# my.net
KiCad netlist of a schematic drawn in EAGLE
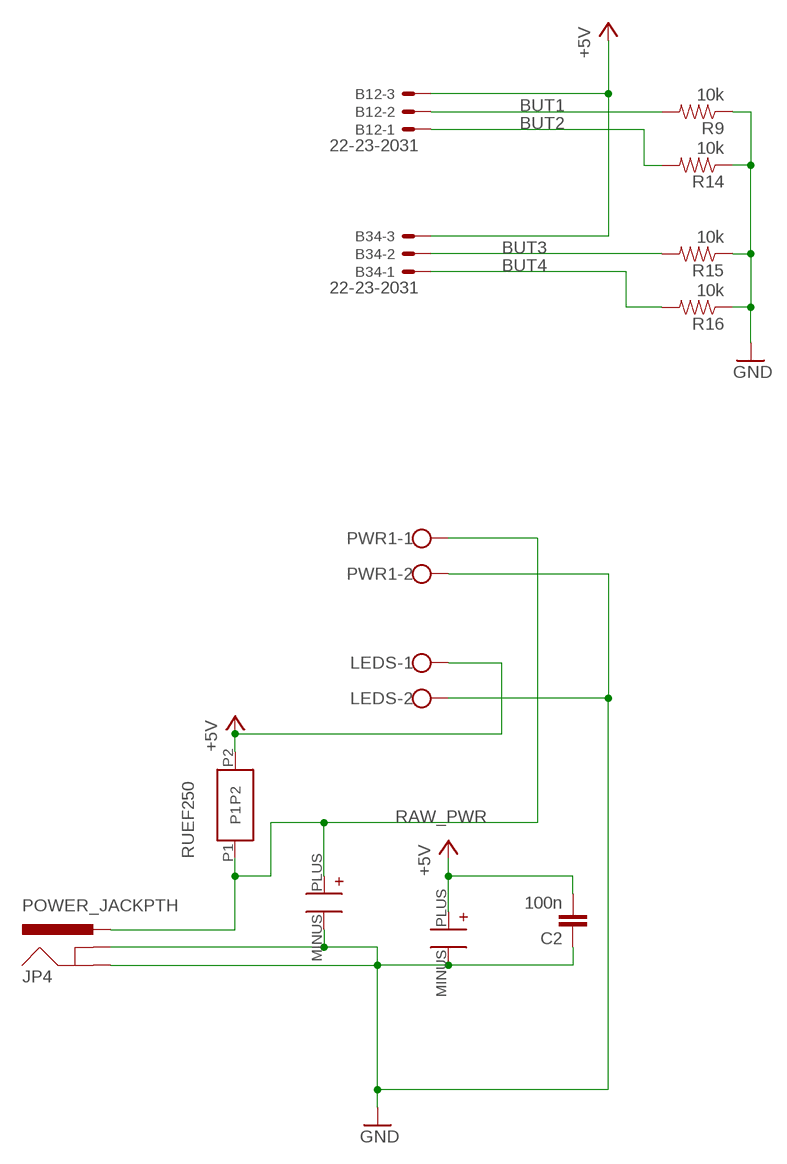
[diagram p0: schematic, sheet 1, part 1 of 2]
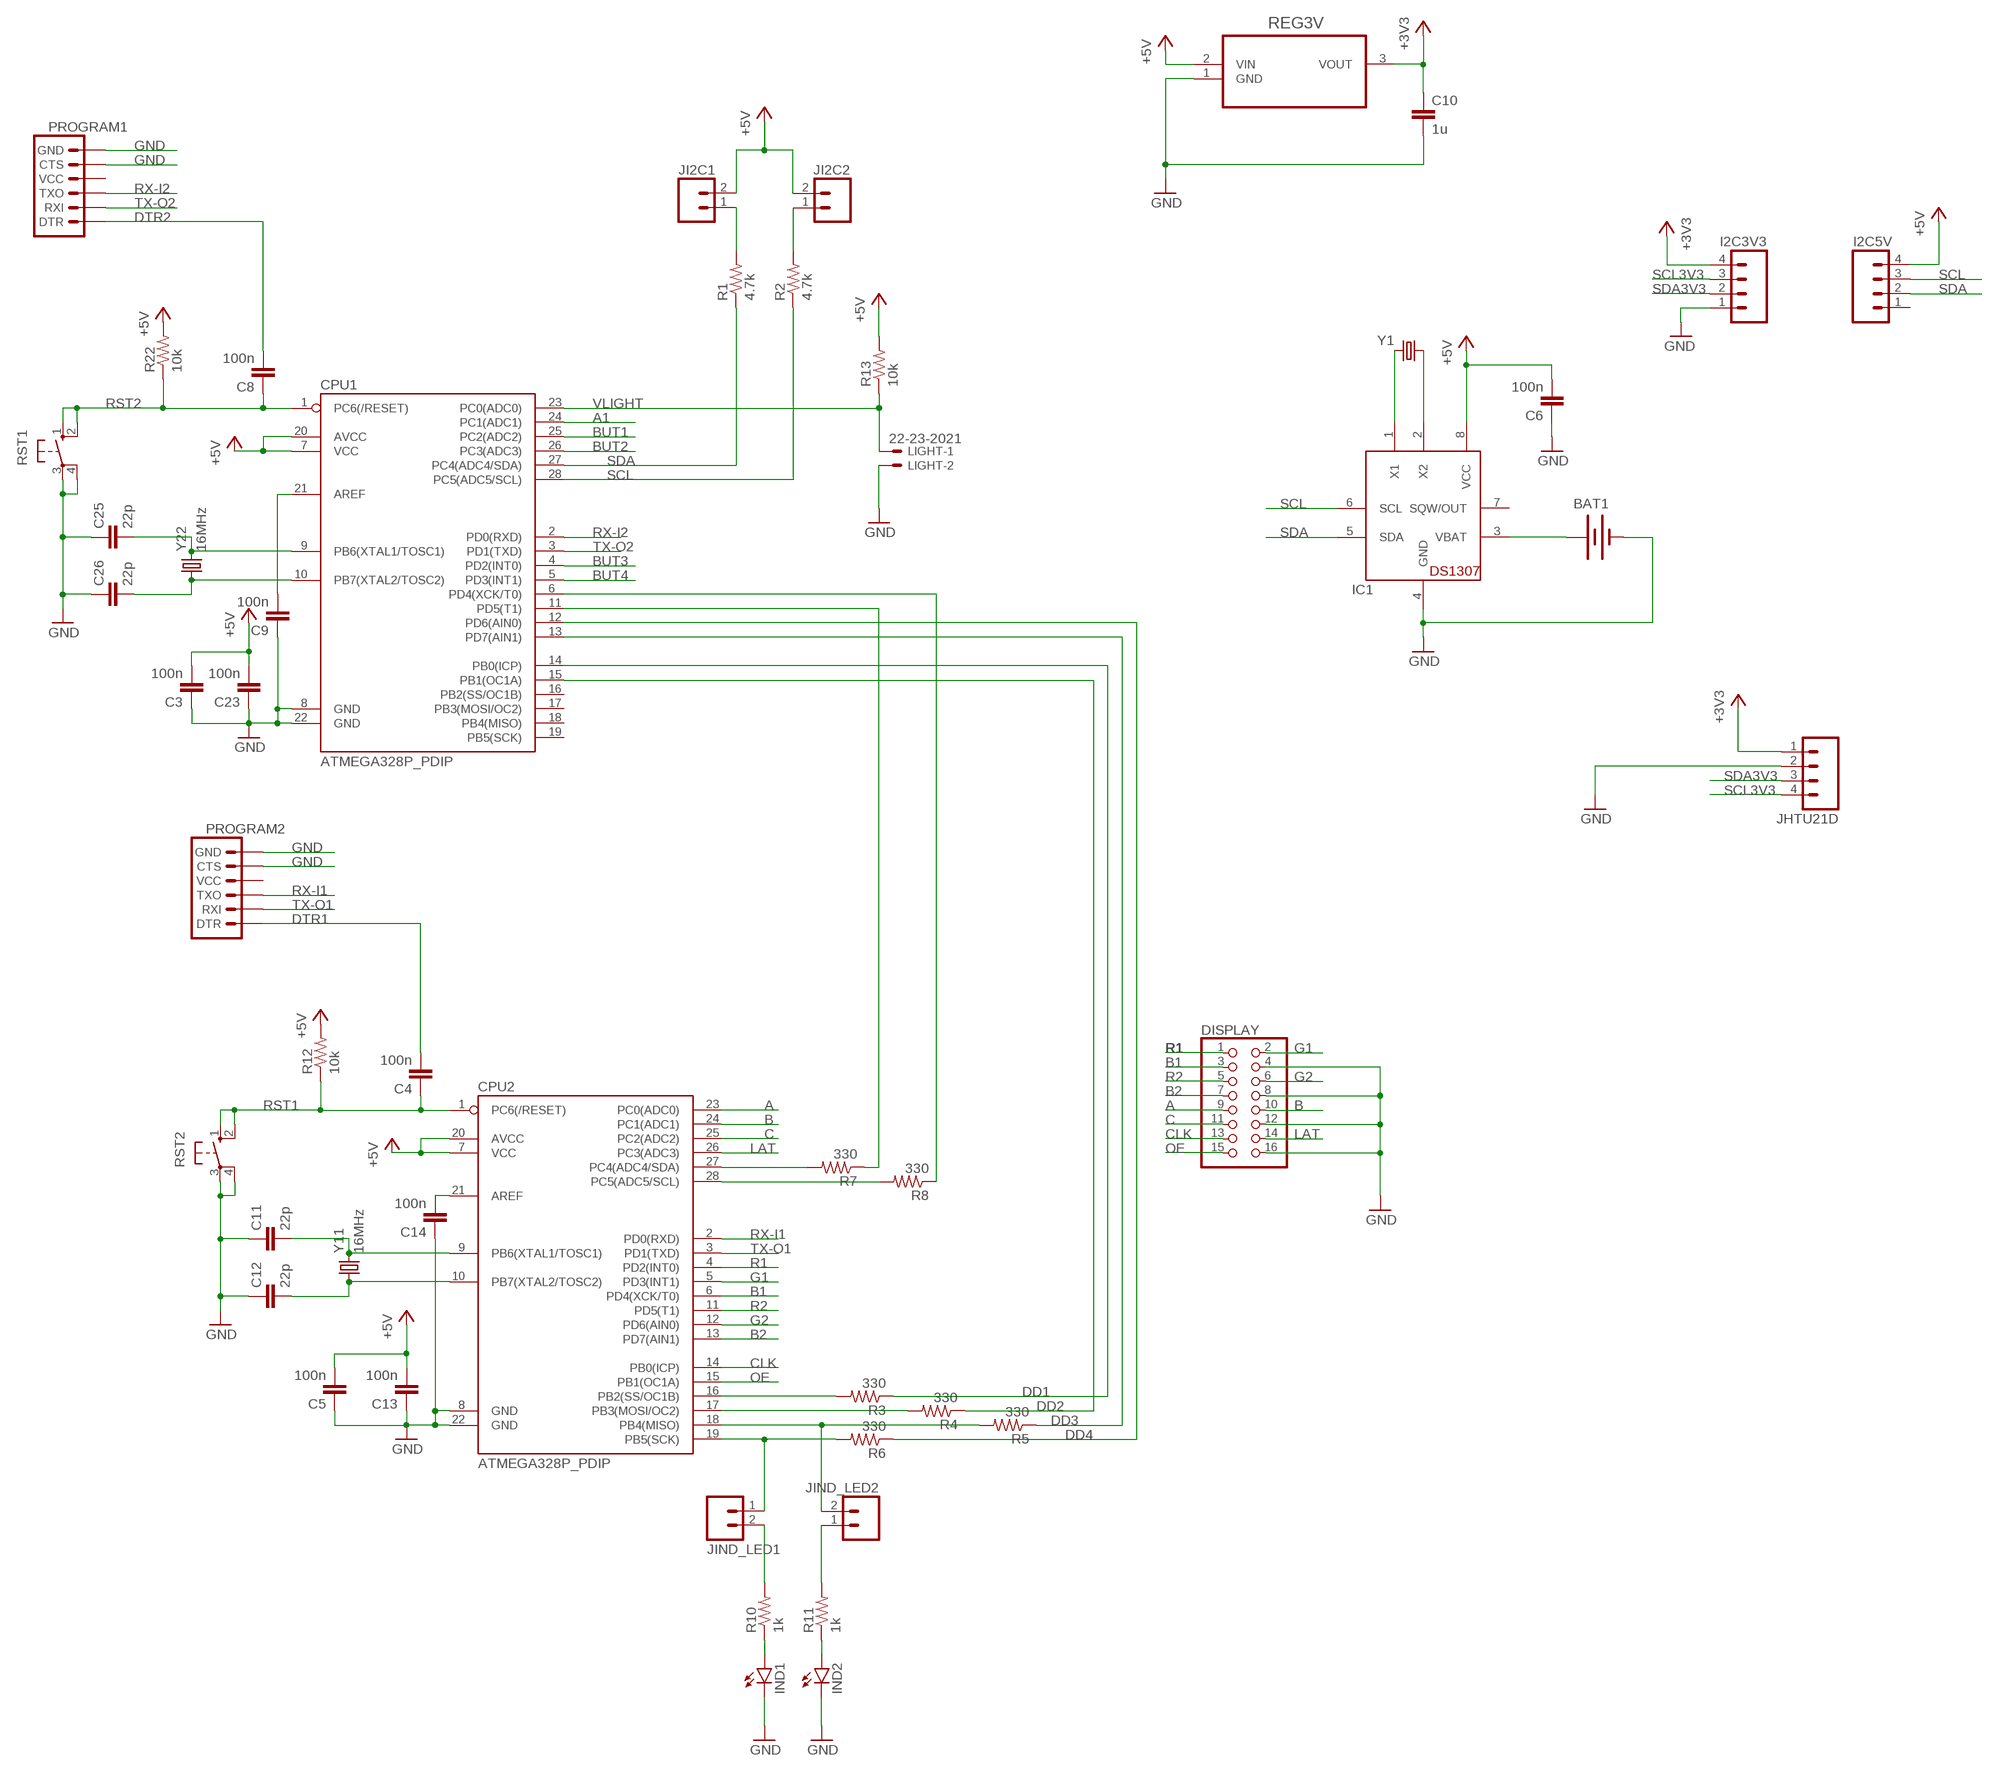
[diagram p1: schematic, sheet 1, part 2 of 2]

(export (version "E")
  (design (tool "Eeschema 10.0.6"))
  (components
    (comp (ref "B12")
      (value "22-23-2031")
      (footprint "eagle-import:22-23-2031")
      (fields (field (name "MF") "MOLEX"))
      (libsource (lib "eagle-import") (part "22-23-2031"))
    )
    (comp (ref "B34")
      (value "22-23-2031")
      (footprint "eagle-import:22-23-2031")
      (fields (field (name "MF") "MOLEX"))
      (libsource (lib "eagle-import") (part "22-23-2031"))
    )
    (comp (ref "BAT1")
      (value "BATTERY12MM")
      (footprint "eagle-import:BATTCON_12MM")
      (libsource (lib "eagle-import") (part "BATTERY12MM"))
    )
    (comp (ref "C1")
      (value "EEU-FR1C471B")
      (footprint "eagle-import:EEU-FR1C471B")
      (libsource (lib "eagle-import") (part "EEU-FR1C471B"))
    )
    (comp (ref "C2")
      (value "100n")
      (footprint "eagle-import:C025-024X044")
      (libsource (lib "eagle-import") (part "C-EU025-024X044"))
    )
    (comp (ref "C3")
      (value "100n")
      (footprint "eagle-import:C025-024X044")
      (libsource (lib "eagle-import") (part "C-EU025-024X044"))
    )
    (comp (ref "C4")
      (value "100n")
      (footprint "eagle-import:C025-024X044")
      (libsource (lib "eagle-import") (part "C-EU025-024X044"))
    )
    (comp (ref "C5")
      (value "100n")
      (footprint "eagle-import:C025-024X044")
      (libsource (lib "eagle-import") (part "C-EU025-024X044"))
    )
    (comp (ref "C6")
      (value "100n")
      (footprint "eagle-import:C025-024X044")
      (libsource (lib "eagle-import") (part "C-EU025-024X044"))
    )
    (comp (ref "C7")
      (value "EEU-FR1C471B")
      (footprint "eagle-import:EEU-FR1C471B")
      (libsource (lib "eagle-import") (part "EEU-FR1C471B"))
    )
    (comp (ref "C8")
      (value "100n")
      (footprint "eagle-import:C025-024X044")
      (libsource (lib "eagle-import") (part "C-EU025-024X044"))
    )
    (comp (ref "C9")
      (value "100n")
      (footprint "eagle-import:C025-024X044")
      (libsource (lib "eagle-import") (part "C-EU025-024X044"))
    )
    (comp (ref "C10")
      (value "1u")
      (footprint "eagle-import:AXIAL-5MM")
      (libsource (lib "eagle-import") (part "CAP_"))
    )
    (comp (ref "C11")
      (value "22p")
      (footprint "eagle-import:C025-024X044")
      (libsource (lib "eagle-import") (part "C-EU025-024X044"))
    )
    (comp (ref "C12")
      (value "22p")
      (footprint "eagle-import:C025-024X044")
      (libsource (lib "eagle-import") (part "C-EU025-024X044"))
    )
    (comp (ref "C13")
      (value "100n")
      (footprint "eagle-import:C025-024X044")
      (libsource (lib "eagle-import") (part "C-EU025-024X044"))
    )
    (comp (ref "C14")
      (value "100n")
      (footprint "eagle-import:C025-024X044")
      (libsource (lib "eagle-import") (part "C-EU025-024X044"))
    )
    (comp (ref "C23")
      (value "100n")
      (footprint "eagle-import:C025-024X044")
      (libsource (lib "eagle-import") (part "C-EU025-024X044"))
    )
    (comp (ref "C25")
      (value "22p")
      (footprint "eagle-import:C025-024X044")
      (libsource (lib "eagle-import") (part "C-EU025-024X044"))
    )
    (comp (ref "C26")
      (value "22p")
      (footprint "eagle-import:C025-024X044")
      (libsource (lib "eagle-import") (part "C-EU025-024X044"))
    )
    (comp (ref "CPU1")
      (value "ATMEGA328P_PDIP")
      (footprint "eagle-import:DIL28-3")
      (libsource (lib "eagle-import") (part "ATMEGA328P_PDIP"))
    )
    (comp (ref "CPU2")
      (value "ATMEGA328P_PDIP")
      (footprint "eagle-import:DIL28-3")
      (libsource (lib "eagle-import") (part "ATMEGA328P_PDIP"))
    )
    (comp (ref "DISPLAY")
      (value "PINHD-2X8")
      (footprint "eagle-import:2X08")
      (libsource (lib "eagle-import") (part "PINHD-2X8"))
    )
    (comp (ref "I2C3V3")
      (value "M04PTH")
      (footprint "eagle-import:1X04")
      (libsource (lib "eagle-import") (part "M04PTH"))
    )
    (comp (ref "I2C5V")
      (value "M04PTH")
      (footprint "eagle-import:1X04")
      (libsource (lib "eagle-import") (part "M04PTH"))
    )
    (comp (ref "IC1")
      (value "DS1307")
      (footprint "eagle-import:DIL08")
      (libsource (lib "eagle-import") (part "DS1307"))
    )
    (comp (ref "IND1")
      (value "LED5MM")
      (footprint "eagle-import:LED5MM")
      (libsource (lib "eagle-import") (part "LED5MM"))
    )
    (comp (ref "IND2")
      (value "LED5MM")
      (footprint "eagle-import:LED5MM")
      (libsource (lib "eagle-import") (part "LED5MM"))
    )
    (comp (ref "JHTU21D")
      (value "M04PTH")
      (footprint "eagle-import:1X04")
      (libsource (lib "eagle-import") (part "M04PTH"))
    )
    (comp (ref "JI2C1")
      (value "M02PTH")
      (footprint "eagle-import:1X02")
      (libsource (lib "eagle-import") (part "M02PTH"))
    )
    (comp (ref "JI2C2")
      (value "M02PTH")
      (footprint "eagle-import:1X02")
      (libsource (lib "eagle-import") (part "M02PTH"))
    )
    (comp (ref "JIND_LED1")
      (value "M02PTH")
      (footprint "eagle-import:1X02")
      (libsource (lib "eagle-import") (part "M02PTH"))
    )
    (comp (ref "JIND_LED2")
      (value "M02PTH")
      (footprint "eagle-import:1X02")
      (libsource (lib "eagle-import") (part "M02PTH"))
    )
    (comp (ref "JP4")
      (value "POWER_JACKPTH")
      (footprint "eagle-import:POWER_JACK_PTH")
      (libsource (lib "eagle-import") (part "POWER_JACKPTH"))
    )
    (comp (ref "LEDS")
      (value "W237-102")
      (footprint "eagle-import:W237-102")
      (fields (field (name "MPN") "237-102"))
      (libsource (lib "eagle-import") (part "W237-102"))
    )
    (comp (ref "LIGHT")
      (value "22-23-2021")
      (footprint "eagle-import:22-23-2021")
      (fields (field (name "MF") "MOLEX"))
      (libsource (lib "eagle-import") (part "22-23-2021"))
    )
    (comp (ref "PROGRAM1")
      (value "ARDUINO_SERIAL_PROGRAMPTH")
      (footprint "eagle-import:1X06")
      (libsource (lib "eagle-import") (part "ARDUINO_SERIAL_PROGRAMPTH"))
    )
    (comp (ref "PROGRAM2")
      (value "ARDUINO_SERIAL_PROGRAMPTH")
      (footprint "eagle-import:1X06")
      (libsource (lib "eagle-import") (part "ARDUINO_SERIAL_PROGRAMPTH"))
    )
    (comp (ref "PWR1")
      (value "W237-102")
      (footprint "eagle-import:W237-102")
      (fields (field (name "MPN") "237-102"))
      (libsource (lib "eagle-import") (part "W237-102"))
    )
    (comp (ref "R1")
      (value "4.7k")
      (footprint "eagle-import:AXIAL-0.3")
      (libsource (lib "eagle-import") (part "RESISTORAXIAL-0.3"))
    )
    (comp (ref "R2")
      (value "4.7k")
      (footprint "eagle-import:AXIAL-0.3")
      (libsource (lib "eagle-import") (part "RESISTORAXIAL-0.3"))
    )
    (comp (ref "R3")
      (value "330")
      (footprint "eagle-import:AXIAL-0.3")
      (libsource (lib "eagle-import") (part "RESISTORAXIAL-0.3"))
    )
    (comp (ref "R4")
      (value "330")
      (footprint "eagle-import:AXIAL-0.3")
      (libsource (lib "eagle-import") (part "RESISTORAXIAL-0.3"))
    )
    (comp (ref "R5")
      (value "330")
      (footprint "eagle-import:AXIAL-0.3")
      (libsource (lib "eagle-import") (part "RESISTORAXIAL-0.3"))
    )
    (comp (ref "R6")
      (value "330")
      (footprint "eagle-import:AXIAL-0.3")
      (libsource (lib "eagle-import") (part "RESISTORAXIAL-0.3"))
    )
    (comp (ref "R7")
      (value "330")
      (footprint "eagle-import:AXIAL-0.3")
      (libsource (lib "eagle-import") (part "RESISTORAXIAL-0.3"))
    )
    (comp (ref "R8")
      (value "330")
      (footprint "eagle-import:AXIAL-0.3")
      (libsource (lib "eagle-import") (part "RESISTORAXIAL-0.3"))
    )
    (comp (ref "R9")
      (value "10k")
      (footprint "eagle-import:AXIAL-0.3")
      (libsource (lib "eagle-import") (part "RESISTORAXIAL-0.3"))
    )
    (comp (ref "R10")
      (value "1k")
      (footprint "eagle-import:AXIAL-0.3")
      (libsource (lib "eagle-import") (part "RESISTORAXIAL-0.3"))
    )
    (comp (ref "R11")
      (value "1k")
      (footprint "eagle-import:AXIAL-0.3")
      (libsource (lib "eagle-import") (part "RESISTORAXIAL-0.3"))
    )
    (comp (ref "R12")
      (value "10k")
      (footprint "eagle-import:AXIAL-0.3")
      (libsource (lib "eagle-import") (part "RESISTORAXIAL-0.3"))
    )
    (comp (ref "R13")
      (value "10k")
      (footprint "eagle-import:AXIAL-0.3")
      (libsource (lib "eagle-import") (part "RESISTORAXIAL-0.3"))
    )
    (comp (ref "R14")
      (value "10k")
      (footprint "eagle-import:AXIAL-0.3")
      (libsource (lib "eagle-import") (part "RESISTORAXIAL-0.3"))
    )
    (comp (ref "R15")
      (value "10k")
      (footprint "eagle-import:AXIAL-0.3")
      (libsource (lib "eagle-import") (part "RESISTORAXIAL-0.3"))
    )
    (comp (ref "R16")
      (value "10k")
      (footprint "eagle-import:AXIAL-0.3")
      (libsource (lib "eagle-import") (part "RESISTORAXIAL-0.3"))
    )
    (comp (ref "R22")
      (value "10k")
      (footprint "eagle-import:AXIAL-0.3")
      (libsource (lib "eagle-import") (part "RESISTORAXIAL-0.3"))
    )
    (comp (ref "REG3V")
      (value "MCP1700-3002E/TO")
      (footprint "eagle-import:TO127P254X495-3")
      (libsource (lib "eagle-import") (part "MCP1700-3002E/TO"))
    )
    (comp (ref "RST1")
      (value "10-XX")
      (footprint "eagle-import:B3F-10XX")
      (fields (field (name "MPN") "B3F-1000"))
      (libsource (lib "eagle-import") (part "10-XX"))
    )
    (comp (ref "RST2")
      (value "10-XX")
      (footprint "eagle-import:B3F-10XX")
      (fields (field (name "MPN") "B3F-1000"))
      (libsource (lib "eagle-import") (part "10-XX"))
    )
    (comp (ref "RUEF250")
      (value "RUEF250U")
      (footprint "eagle-import:RUEF250U")
      (libsource (lib "eagle-import") (part "RUEF250U"))
    )
    (comp (ref "Y1")
      (value "CRYSTAL32-SMD")
      (footprint "eagle-import:CRYSTAL-32KHZ-SMD")
      (libsource (lib "eagle-import") (part "CRYSTAL32-SMD"))
    )
    (comp (ref "Y11")
      (value "16MHz")
      (footprint "eagle-import:HC49US")
      (libsource (lib "eagle-import") (part "CRYSTALHC49US"))
    )
    (comp (ref "Y22")
      (value "16MHz")
      (footprint "eagle-import:HC49US")
      (libsource (lib "eagle-import") (part "CRYSTALHC49US"))
    )
  )
  (nets
    (net (code "1") (name "+3V3") (class "Default")
      (node (ref "C10") (pin "P$1") (pinfunction "1_P$1") (pintype "passive"))
      (node (ref "I2C3V3") (pin "4") (pinfunction "4_4") (pintype "passive"))
      (node (ref "JHTU21D") (pin "1") (pinfunction "1_1") (pintype "passive"))
      (node (ref "REG3V") (pin "3") (pinfunction "VOUT_3") (pintype "output"))
    )
    (net (code "2") (name "+5V") (class "Default")
      (node (ref "B12") (pin "3") (pinfunction "S_3") (pintype "passive"))
      (node (ref "B34") (pin "3") (pinfunction "S_3") (pintype "passive"))
      (node (ref "C1") (pin "PLUS") (pinfunction "PLUS_PLUS") (pintype "bidirectional"))
      (node (ref "C13") (pin "2") (pinfunction "2_2") (pintype "passive"))
      (node (ref "C2") (pin "2") (pinfunction "2_2") (pintype "passive"))
      (node (ref "C23") (pin "2") (pinfunction "2_2") (pintype "passive"))
      (node (ref "C3") (pin "2") (pinfunction "2_2") (pintype "passive"))
      (node (ref "C5") (pin "2") (pinfunction "2_2") (pintype "passive"))
      (node (ref "C6") (pin "2") (pinfunction "2_2") (pintype "passive"))
      (node (ref "CPU1") (pin "20") (pinfunction "AVCC_20") (pintype "bidirectional"))
      (node (ref "CPU1") (pin "7") (pinfunction "VCC_7") (pintype "bidirectional"))
      (node (ref "CPU2") (pin "20") (pinfunction "AVCC_20") (pintype "bidirectional"))
      (node (ref "CPU2") (pin "7") (pinfunction "VCC_7") (pintype "bidirectional"))
      (node (ref "I2C5V") (pin "4") (pinfunction "4_4") (pintype "passive"))
      (node (ref "IC1") (pin "8") (pinfunction "VCC_8") (pintype "power_in"))
      (node (ref "JI2C1") (pin "2") (pinfunction "2_2") (pintype "passive"))
      (node (ref "JI2C2") (pin "2") (pinfunction "2_2") (pintype "passive"))
      (node (ref "LEDS") (pin "1") (pinfunction "KL_1") (pintype "passive"))
      (node (ref "R12") (pin "P$2") (pinfunction "2_P$2") (pintype "passive"))
      (node (ref "R13") (pin "P$2") (pinfunction "2_P$2") (pintype "passive"))
      (node (ref "R22") (pin "P$2") (pinfunction "2_P$2") (pintype "passive"))
      (node (ref "REG3V") (pin "2") (pinfunction "VIN_2") (pintype "input"))
      (node (ref "RUEF250") (pin "P2") (pinfunction "P2_P2") (pintype "bidirectional"))
    )
    (net (code "3") (name "/A") (class "Default")
      (node (ref "CPU2") (pin "23") (pinfunction "PC0(ADC0)_23") (pintype "bidirectional"))
      (node (ref "DISPLAY") (pin "9") (pinfunction "9_9") (pintype "passive"))
    )
    (net (code "4") (name "/A1") (class "Default")
      (node (ref "CPU1") (pin "24") (pinfunction "PC1(ADC1)_24") (pintype "bidirectional"))
    )
    (net (code "5") (name "/B") (class "Default")
      (node (ref "CPU2") (pin "24") (pinfunction "PC1(ADC1)_24") (pintype "bidirectional"))
      (node (ref "DISPLAY") (pin "10") (pinfunction "10_10") (pintype "passive"))
    )
    (net (code "6") (name "/B1") (class "Default")
      (node (ref "CPU2") (pin "6") (pinfunction "PD4(XCK/T0)_6") (pintype "bidirectional"))
      (node (ref "DISPLAY") (pin "3") (pinfunction "3_3") (pintype "passive"))
    )
    (net (code "7") (name "/B2") (class "Default")
      (node (ref "CPU2") (pin "13") (pinfunction "PD7(AIN1)_13") (pintype "bidirectional"))
      (node (ref "DISPLAY") (pin "7") (pinfunction "7_7") (pintype "passive"))
    )
    (net (code "8") (name "/BUT1") (class "Default")
      (node (ref "B12") (pin "2") (pinfunction "S_2") (pintype "passive"))
      (node (ref "CPU1") (pin "25") (pinfunction "PC2(ADC2)_25") (pintype "bidirectional"))
      (node (ref "R9") (pin "P$2") (pinfunction "2_P$2") (pintype "passive"))
    )
    (net (code "9") (name "/BUT2") (class "Default")
      (node (ref "B12") (pin "1") (pinfunction "S_1") (pintype "passive"))
      (node (ref "CPU1") (pin "26") (pinfunction "PC3(ADC3)_26") (pintype "bidirectional"))
      (node (ref "R14") (pin "P$2") (pinfunction "2_P$2") (pintype "passive"))
    )
    (net (code "10") (name "/BUT3") (class "Default")
      (node (ref "B34") (pin "2") (pinfunction "S_2") (pintype "passive"))
      (node (ref "CPU1") (pin "4") (pinfunction "PD2(INT0)_4") (pintype "bidirectional"))
      (node (ref "R15") (pin "P$2") (pinfunction "2_P$2") (pintype "passive"))
    )
    (net (code "11") (name "/BUT4") (class "Default")
      (node (ref "B34") (pin "1") (pinfunction "S_1") (pintype "passive"))
      (node (ref "CPU1") (pin "5") (pinfunction "PD3(INT1)_5") (pintype "bidirectional"))
      (node (ref "R16") (pin "P$2") (pinfunction "2_P$2") (pintype "passive"))
    )
    (net (code "12") (name "/C") (class "Default")
      (node (ref "CPU2") (pin "25") (pinfunction "PC2(ADC2)_25") (pintype "bidirectional"))
      (node (ref "DISPLAY") (pin "11") (pinfunction "11_11") (pintype "passive"))
    )
    (net (code "13") (name "/CLK") (class "Default")
      (node (ref "CPU2") (pin "14") (pinfunction "PB0(ICP)_14") (pintype "bidirectional"))
      (node (ref "DISPLAY") (pin "13") (pinfunction "13_13") (pintype "passive"))
    )
    (net (code "14") (name "/DD1") (class "Default")
      (node (ref "CPU1") (pin "14") (pinfunction "PB0(ICP)_14") (pintype "bidirectional"))
      (node (ref "R3") (pin "P$1") (pinfunction "1_P$1") (pintype "passive"))
    )
    (net (code "15") (name "/DD2") (class "Default")
      (node (ref "CPU1") (pin "15") (pinfunction "PB1(OC1A)_15") (pintype "bidirectional"))
      (node (ref "R4") (pin "P$1") (pinfunction "1_P$1") (pintype "passive"))
    )
    (net (code "16") (name "/DD3") (class "Default")
      (node (ref "CPU1") (pin "13") (pinfunction "PD7(AIN1)_13") (pintype "bidirectional"))
      (node (ref "R5") (pin "P$1") (pinfunction "1_P$1") (pintype "passive"))
    )
    (net (code "17") (name "/DD4") (class "Default")
      (node (ref "CPU1") (pin "12") (pinfunction "PD6(AIN0)_12") (pintype "bidirectional"))
      (node (ref "R6") (pin "P$1") (pinfunction "1_P$1") (pintype "passive"))
    )
    (net (code "18") (name "/DTR1") (class "Default")
      (node (ref "C4") (pin "2") (pinfunction "2_2") (pintype "passive"))
      (node (ref "PROGRAM2") (pin "1") (pinfunction "DTR_1") (pintype "passive"))
    )
    (net (code "19") (name "/DTR2") (class "Default")
      (node (ref "C8") (pin "2") (pinfunction "2_2") (pintype "passive"))
      (node (ref "PROGRAM1") (pin "1") (pinfunction "DTR_1") (pintype "passive"))
    )
    (net (code "20") (name "/G1") (class "Default")
      (node (ref "CPU2") (pin "5") (pinfunction "PD3(INT1)_5") (pintype "bidirectional"))
      (node (ref "DISPLAY") (pin "2") (pinfunction "2_2") (pintype "passive"))
    )
    (net (code "21") (name "/G2") (class "Default")
      (node (ref "CPU2") (pin "12") (pinfunction "PD6(AIN0)_12") (pintype "bidirectional"))
      (node (ref "DISPLAY") (pin "6") (pinfunction "6_6") (pintype "passive"))
    )
    (net (code "22") (name "/LAT") (class "Default")
      (node (ref "CPU2") (pin "26") (pinfunction "PC3(ADC3)_26") (pintype "bidirectional"))
      (node (ref "DISPLAY") (pin "14") (pinfunction "14_14") (pintype "passive"))
    )
    (net (code "23") (name "/OE") (class "Default")
      (node (ref "CPU2") (pin "15") (pinfunction "PB1(OC1A)_15") (pintype "bidirectional"))
      (node (ref "DISPLAY") (pin "15") (pinfunction "15_15") (pintype "passive"))
    )
    (net (code "24") (name "/R1") (class "Default")
      (node (ref "CPU2") (pin "4") (pinfunction "PD2(INT0)_4") (pintype "bidirectional"))
      (node (ref "DISPLAY") (pin "1") (pinfunction "1_1") (pintype "passive"))
    )
    (net (code "25") (name "/R2") (class "Default")
      (node (ref "CPU2") (pin "11") (pinfunction "PD5(T1)_11") (pintype "bidirectional"))
      (node (ref "DISPLAY") (pin "5") (pinfunction "5_5") (pintype "passive"))
    )
    (net (code "26") (name "/RAW_PWR") (class "Default")
      (node (ref "C7") (pin "PLUS") (pinfunction "PLUS_PLUS") (pintype "bidirectional"))
      (node (ref "JP4") (pin "PWR") (pinfunction "PWR_PWR") (pintype "bidirectional"))
      (node (ref "PWR1") (pin "1") (pinfunction "KL_1") (pintype "passive"))
      (node (ref "RUEF250") (pin "P1") (pinfunction "P1_P1") (pintype "bidirectional"))
    )
    (net (code "27") (name "/RST1") (class "Default")
      (node (ref "C4") (pin "1") (pinfunction "1_1") (pintype "passive"))
      (node (ref "CPU2") (pin "1") (pinfunction "PC6(/RESET)_1") (pintype "bidirectional"))
      (node (ref "R12") (pin "P$1") (pinfunction "1_P$1") (pintype "passive"))
      (node (ref "RST2") (pin "1") (pinfunction "S_1") (pintype "passive"))
      (node (ref "RST2") (pin "2") (pinfunction "S1_2") (pintype "passive"))
    )
    (net (code "28") (name "/RST2") (class "Default")
      (node (ref "C8") (pin "1") (pinfunction "1_1") (pintype "passive"))
      (node (ref "CPU1") (pin "1") (pinfunction "PC6(/RESET)_1") (pintype "bidirectional"))
      (node (ref "R22") (pin "P$1") (pinfunction "1_P$1") (pintype "passive"))
      (node (ref "RST1") (pin "1") (pinfunction "S_1") (pintype "passive"))
      (node (ref "RST1") (pin "2") (pinfunction "S1_2") (pintype "passive"))
    )
    (net (code "29") (name "/RX-I1") (class "Default")
      (node (ref "CPU2") (pin "2") (pinfunction "PD0(RXD)_2") (pintype "bidirectional"))
      (node (ref "PROGRAM2") (pin "3") (pinfunction "TXO_3") (pintype "passive"))
    )
    (net (code "30") (name "/RX-I2") (class "Default")
      (node (ref "CPU1") (pin "2") (pinfunction "PD0(RXD)_2") (pintype "bidirectional"))
      (node (ref "PROGRAM1") (pin "3") (pinfunction "TXO_3") (pintype "passive"))
    )
    (net (code "31") (name "/SCL") (class "Default")
      (node (ref "CPU1") (pin "28") (pinfunction "PC5(ADC5/SCL)_28") (pintype "bidirectional"))
      (node (ref "I2C5V") (pin "3") (pinfunction "3_3") (pintype "passive"))
      (node (ref "IC1") (pin "6") (pinfunction "SCL_6") (pintype "bidirectional"))
      (node (ref "R2") (pin "P$1") (pinfunction "1_P$1") (pintype "passive"))
    )
    (net (code "32") (name "/SCL3V3") (class "Default")
      (node (ref "I2C3V3") (pin "3") (pinfunction "3_3") (pintype "passive"))
      (node (ref "JHTU21D") (pin "4") (pinfunction "4_4") (pintype "passive"))
    )
    (net (code "33") (name "/SDA") (class "Default")
      (node (ref "CPU1") (pin "27") (pinfunction "PC4(ADC4/SDA)_27") (pintype "bidirectional"))
      (node (ref "I2C5V") (pin "2") (pinfunction "2_2") (pintype "passive"))
      (node (ref "IC1") (pin "5") (pinfunction "SDA_5") (pintype "bidirectional"))
      (node (ref "R1") (pin "P$1") (pinfunction "1_P$1") (pintype "passive"))
    )
    (net (code "34") (name "/SDA3V3") (class "Default")
      (node (ref "I2C3V3") (pin "2") (pinfunction "2_2") (pintype "passive"))
      (node (ref "JHTU21D") (pin "3") (pinfunction "3_3") (pintype "passive"))
    )
    (net (code "35") (name "/TX-O1") (class "Default")
      (node (ref "CPU2") (pin "3") (pinfunction "PD1(TXD)_3") (pintype "bidirectional"))
      (node (ref "PROGRAM2") (pin "2") (pinfunction "RXI_2") (pintype "passive"))
    )
    (net (code "36") (name "/TX-O2") (class "Default")
      (node (ref "CPU1") (pin "3") (pinfunction "PD1(TXD)_3") (pintype "bidirectional"))
      (node (ref "PROGRAM1") (pin "2") (pinfunction "RXI_2") (pintype "passive"))
    )
    (net (code "37") (name "/VLIGHT") (class "Default")
      (node (ref "CPU1") (pin "23") (pinfunction "PC0(ADC0)_23") (pintype "bidirectional"))
      (node (ref "LIGHT") (pin "1") (pinfunction "S_1") (pintype "passive"))
      (node (ref "R13") (pin "P$1") (pinfunction "1_P$1") (pintype "passive"))
    )
    (net (code "38") (name "GND") (class "Default")
      (node (ref "BAT1") (pin "GND") (pinfunction "-_GND") (pintype "power_in"))
      (node (ref "C1") (pin "MINUS") (pinfunction "MINUS_MINUS") (pintype "bidirectional"))
      (node (ref "C10") (pin "P$2") (pinfunction "2_P$2") (pintype "passive"))
      (node (ref "C11") (pin "1") (pinfunction "1_1") (pintype "passive"))
      (node (ref "C12") (pin "1") (pinfunction "1_1") (pintype "passive"))
      (node (ref "C13") (pin "1") (pinfunction "1_1") (pintype "passive"))
      (node (ref "C14") (pin "1") (pinfunction "1_1") (pintype "passive"))
      (node (ref "C2") (pin "1") (pinfunction "1_1") (pintype "passive"))
      (node (ref "C23") (pin "1") (pinfunction "1_1") (pintype "passive"))
      (node (ref "C25") (pin "1") (pinfunction "1_1") (pintype "passive"))
      (node (ref "C26") (pin "1") (pinfunction "1_1") (pintype "passive"))
      (node (ref "C3") (pin "1") (pinfunction "1_1") (pintype "passive"))
      (node (ref "C5") (pin "1") (pinfunction "1_1") (pintype "passive"))
      (node (ref "C6") (pin "1") (pinfunction "1_1") (pintype "passive"))
      (node (ref "C7") (pin "MINUS") (pinfunction "MINUS_MINUS") (pintype "bidirectional"))
      (node (ref "C9") (pin "1") (pinfunction "1_1") (pintype "passive"))
      (node (ref "CPU1") (pin "22") (pinfunction "GND_22") (pintype "bidirectional"))
      (node (ref "CPU1") (pin "8") (pinfunction "GND_8") (pintype "bidirectional"))
      (node (ref "CPU2") (pin "22") (pinfunction "GND_22") (pintype "bidirectional"))
      (node (ref "CPU2") (pin "8") (pinfunction "GND_8") (pintype "bidirectional"))
      (node (ref "DISPLAY") (pin "12") (pinfunction "12_12") (pintype "passive"))
      (node (ref "DISPLAY") (pin "16") (pinfunction "16_16") (pintype "passive"))
      (node (ref "DISPLAY") (pin "4") (pinfunction "4_4") (pintype "passive"))
      (node (ref "DISPLAY") (pin "8") (pinfunction "8_8") (pintype "passive"))
      (node (ref "I2C3V3") (pin "1") (pinfunction "1_1") (pintype "passive"))
      (node (ref "IC1") (pin "4") (pinfunction "GND_4") (pintype "power_in"))
      (node (ref "IND1") (pin "K") (pinfunction "C_K") (pintype "passive"))
      (node (ref "IND2") (pin "K") (pinfunction "C_K") (pintype "passive"))
      (node (ref "JHTU21D") (pin "2") (pinfunction "2_2") (pintype "passive"))
      (node (ref "JP4") (pin "GND") (pinfunction "GND_GND") (pintype "bidirectional"))
      (node (ref "JP4") (pin "GNDBREAK") (pinfunction "GNDBREAK_GNDBREAK") (pintype "bidirectional"))
      (node (ref "LEDS") (pin "2") (pinfunction "KL_2") (pintype "passive"))
      (node (ref "LIGHT") (pin "2") (pinfunction "S_2") (pintype "passive"))
      (node (ref "PROGRAM1") (pin "5") (pinfunction "CTS_5") (pintype "passive"))
      (node (ref "PROGRAM1") (pin "6") (pinfunction "GND_6") (pintype "passive"))
      (node (ref "PROGRAM2") (pin "5") (pinfunction "CTS_5") (pintype "passive"))
      (node (ref "PROGRAM2") (pin "6") (pinfunction "GND_6") (pintype "passive"))
      (node (ref "PWR1") (pin "2") (pinfunction "KL_2") (pintype "passive"))
      (node (ref "R14") (pin "P$1") (pinfunction "1_P$1") (pintype "passive"))
      (node (ref "R15") (pin "P$1") (pinfunction "1_P$1") (pintype "passive"))
      (node (ref "R16") (pin "P$1") (pinfunction "1_P$1") (pintype "passive"))
      (node (ref "R9") (pin "P$1") (pinfunction "1_P$1") (pintype "passive"))
      (node (ref "REG3V") (pin "1") (pinfunction "GND_1") (pintype "passive"))
      (node (ref "RST1") (pin "3") (pinfunction "P_3") (pintype "passive"))
      (node (ref "RST1") (pin "4") (pinfunction "P1_4") (pintype "passive"))
      (node (ref "RST2") (pin "3") (pinfunction "P_3") (pintype "passive"))
      (node (ref "RST2") (pin "4") (pinfunction "P1_4") (pintype "passive"))
    )
    (net (code "39") (name "Net-(BAT1-+)") (class "Default")
      (node (ref "BAT1") (pin "PWR@1") (pinfunction "+_PWR@1") (pintype "power_in"))
      (node (ref "IC1") (pin "3") (pinfunction "VBAT_3") (pintype "power_in"))
    )
    (net (code "40") (name "Net-(CPU1-AREF)") (class "Default")
      (node (ref "C9") (pin "2") (pinfunction "2_2") (pintype "passive"))
      (node (ref "CPU1") (pin "21") (pinfunction "AREF_21") (pintype "bidirectional"))
    )
    (net (code "41") (name "Net-(CPU1-PB6(XTAL1{slash}TOSC1))") (class "Default")
      (node (ref "C25") (pin "2") (pinfunction "2_2") (pintype "passive"))
      (node (ref "CPU1") (pin "9") (pinfunction "PB6(XTAL1/TOSC1)_9") (pintype "bidirectional"))
      (node (ref "Y22") (pin "2") (pinfunction "2_2") (pintype "passive"))
    )
    (net (code "42") (name "Net-(CPU1-PB7(XTAL2{slash}TOSC2))") (class "Default")
      (node (ref "C26") (pin "2") (pinfunction "2_2") (pintype "passive"))
      (node (ref "CPU1") (pin "10") (pinfunction "PB7(XTAL2/TOSC2)_10") (pintype "bidirectional"))
      (node (ref "Y22") (pin "1") (pinfunction "1_1") (pintype "passive"))
    )
    (net (code "43") (name "Net-(CPU1-PD4(XCK{slash}T0))") (class "Default")
      (node (ref "CPU1") (pin "6") (pinfunction "PD4(XCK/T0)_6") (pintype "bidirectional"))
      (node (ref "R8") (pin "P$1") (pinfunction "1_P$1") (pintype "passive"))
    )
    (net (code "44") (name "Net-(CPU1-PD5(T1))") (class "Default")
      (node (ref "CPU1") (pin "11") (pinfunction "PD5(T1)_11") (pintype "bidirectional"))
      (node (ref "R7") (pin "P$1") (pinfunction "1_P$1") (pintype "passive"))
    )
    (net (code "45") (name "Net-(CPU2-AREF)") (class "Default")
      (node (ref "C14") (pin "2") (pinfunction "2_2") (pintype "passive"))
      (node (ref "CPU2") (pin "21") (pinfunction "AREF_21") (pintype "bidirectional"))
    )
    (net (code "46") (name "Net-(CPU2-PB2(SS{slash}OC1B))") (class "Default")
      (node (ref "CPU2") (pin "16") (pinfunction "PB2(SS/OC1B)_16") (pintype "bidirectional"))
      (node (ref "R3") (pin "P$2") (pinfunction "2_P$2") (pintype "passive"))
    )
    (net (code "47") (name "Net-(CPU2-PB3(MOSI{slash}OC2))") (class "Default")
      (node (ref "CPU2") (pin "17") (pinfunction "PB3(MOSI/OC2)_17") (pintype "bidirectional"))
      (node (ref "R4") (pin "P$2") (pinfunction "2_P$2") (pintype "passive"))
    )
    (net (code "48") (name "Net-(CPU2-PB4(MISO))") (class "Default")
      (node (ref "CPU2") (pin "18") (pinfunction "PB4(MISO)_18") (pintype "bidirectional"))
      (node (ref "JIND_LED2") (pin "2") (pinfunction "2_2") (pintype "passive"))
      (node (ref "R5") (pin "P$2") (pinfunction "2_P$2") (pintype "passive"))
    )
    (net (code "49") (name "Net-(CPU2-PB5(SCK))") (class "Default")
      (node (ref "CPU2") (pin "19") (pinfunction "PB5(SCK)_19") (pintype "bidirectional"))
      (node (ref "JIND_LED1") (pin "1") (pinfunction "1_1") (pintype "passive"))
      (node (ref "R6") (pin "P$2") (pinfunction "2_P$2") (pintype "passive"))
    )
    (net (code "50") (name "Net-(CPU2-PB6(XTAL1{slash}TOSC1))") (class "Default")
      (node (ref "C11") (pin "2") (pinfunction "2_2") (pintype "passive"))
      (node (ref "CPU2") (pin "9") (pinfunction "PB6(XTAL1/TOSC1)_9") (pintype "bidirectional"))
      (node (ref "Y11") (pin "2") (pinfunction "2_2") (pintype "passive"))
    )
    (net (code "51") (name "Net-(CPU2-PB7(XTAL2{slash}TOSC2))") (class "Default")
      (node (ref "C12") (pin "2") (pinfunction "2_2") (pintype "passive"))
      (node (ref "CPU2") (pin "10") (pinfunction "PB7(XTAL2/TOSC2)_10") (pintype "bidirectional"))
      (node (ref "Y11") (pin "1") (pinfunction "1_1") (pintype "passive"))
    )
    (net (code "52") (name "Net-(CPU2-PC4(ADC4{slash}SDA))") (class "Default")
      (node (ref "CPU2") (pin "27") (pinfunction "PC4(ADC4/SDA)_27") (pintype "bidirectional"))
      (node (ref "R7") (pin "P$2") (pinfunction "2_P$2") (pintype "passive"))
    )
    (net (code "53") (name "Net-(CPU2-PC5(ADC5{slash}SCL))") (class "Default")
      (node (ref "CPU2") (pin "28") (pinfunction "PC5(ADC5/SCL)_28") (pintype "bidirectional"))
      (node (ref "R8") (pin "P$2") (pinfunction "2_P$2") (pintype "passive"))
    )
    (net (code "54") (name "Net-(IC1-X1)") (class "Default")
      (node (ref "IC1") (pin "1") (pinfunction "X1_1") (pintype "passive"))
      (node (ref "Y1") (pin "X2") (pinfunction "2_X2") (pintype "passive"))
    )
    (net (code "55") (name "Net-(IC1-X2)") (class "Default")
      (node (ref "IC1") (pin "2") (pinfunction "X2_2") (pintype "passive"))
      (node (ref "Y1") (pin "X1") (pinfunction "1_X1") (pintype "passive"))
    )
    (net (code "56") (name "Net-(R1-2)") (class "Default")
      (node (ref "JI2C1") (pin "1") (pinfunction "1_1") (pintype "passive"))
      (node (ref "R1") (pin "P$2") (pinfunction "2_P$2") (pintype "passive"))
    )
    (net (code "57") (name "Net-(R2-2)") (class "Default")
      (node (ref "JI2C2") (pin "1") (pinfunction "1_1") (pintype "passive"))
      (node (ref "R2") (pin "P$2") (pinfunction "2_P$2") (pintype "passive"))
    )
    (net (code "58") (name "Net-(R10-1)") (class "Default")
      (node (ref "IND1") (pin "A") (pinfunction "A_A") (pintype "passive"))
      (node (ref "R10") (pin "P$1") (pinfunction "1_P$1") (pintype "passive"))
    )
    (net (code "59") (name "Net-(R10-2)") (class "Default")
      (node (ref "JIND_LED1") (pin "2") (pinfunction "2_2") (pintype "passive"))
      (node (ref "R10") (pin "P$2") (pinfunction "2_P$2") (pintype "passive"))
    )
    (net (code "60") (name "Net-(R11-1)") (class "Default")
      (node (ref "IND2") (pin "A") (pinfunction "A_A") (pintype "passive"))
      (node (ref "R11") (pin "P$1") (pinfunction "1_P$1") (pintype "passive"))
    )
    (net (code "61") (name "Net-(R11-2)") (class "Default")
      (node (ref "JIND_LED2") (pin "1") (pinfunction "1_1") (pintype "passive"))
      (node (ref "R11") (pin "P$2") (pinfunction "2_P$2") (pintype "passive"))
    )
    (net (code "62") (name "unconnected-(CPU1-PB2(SS{slash}OC1B)-Pad16)") (class "Default")
      (node (ref "CPU1") (pin "16") (pinfunction "PB2(SS/OC1B)_16") (pintype "bidirectional"))
    )
    (net (code "63") (name "unconnected-(CPU1-PB3(MOSI{slash}OC2)-Pad17)") (class "Default")
      (node (ref "CPU1") (pin "17") (pinfunction "PB3(MOSI/OC2)_17") (pintype "bidirectional"))
    )
    (net (code "64") (name "unconnected-(CPU1-PB4(MISO)-Pad18)") (class "Default")
      (node (ref "CPU1") (pin "18") (pinfunction "PB4(MISO)_18") (pintype "bidirectional"))
    )
    (net (code "65") (name "unconnected-(CPU1-PB5(SCK)-Pad19)") (class "Default")
      (node (ref "CPU1") (pin "19") (pinfunction "PB5(SCK)_19") (pintype "bidirectional"))
    )
    (net (code "66") (name "unconnected-(I2C5V-Pad1)") (class "Default")
      (node (ref "I2C5V") (pin "1") (pinfunction "1_1") (pintype "passive"))
    )
    (net (code "67") (name "unconnected-(IC1-SQW{slash}OUT-Pad7)") (class "Default")
      (node (ref "IC1") (pin "7") (pinfunction "SQW/OUT_7") (pintype "bidirectional"))
    )
    (net (code "68") (name "unconnected-(PROGRAM1-VCC-Pad4)") (class "Default")
      (node (ref "PROGRAM1") (pin "4") (pinfunction "VCC_4") (pintype "passive"))
    )
    (net (code "69") (name "unconnected-(PROGRAM2-VCC-Pad4)") (class "Default")
      (node (ref "PROGRAM2") (pin "4") (pinfunction "VCC_4") (pintype "passive"))
    )
  )
)
